# 48V_Converter.net
KiCad netlist of a schematic drawn in Altium Designer
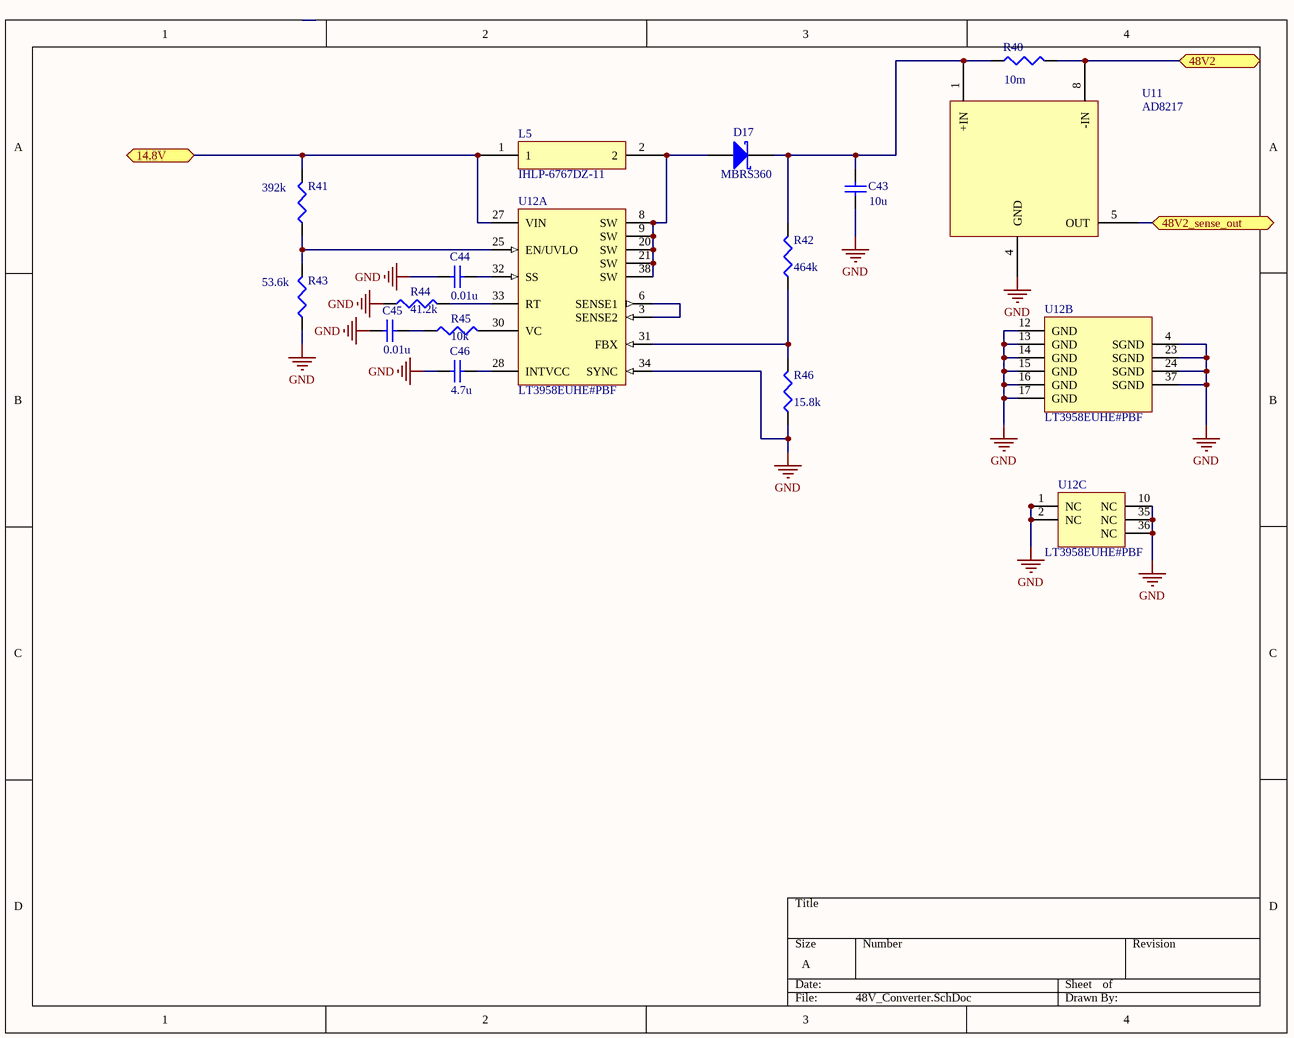
[diagram p0: 48V_Converter.SchDoc]

(export (version "E")
  (design (tool "Eeschema 10.0.6"))
  (components
    (comp (ref "C43")
      (value "10u")
      (footprint "C1206")
      (description "Capacitor (Semiconductor SIM Model)")
      (fields (field (name "Comment") "Cap Semi") (field (name "PUBLISHER") "Altium Limited"))
      (libsource (lib "Miscellaneous Devices") (part "Cap Semi"))
    )
    (comp (ref "C44")
      (value "0.01u")
      (footprint "C1206")
      (description "Capacitor (Semiconductor SIM Model)")
      (fields (field (name "Comment") "Cap Semi") (field (name "PUBLISHER") "Altium Limited"))
      (libsource (lib "Miscellaneous Devices") (part "Cap Semi"))
    )
    (comp (ref "C45")
      (value "0.01u")
      (footprint "C1206")
      (description "Capacitor (Semiconductor SIM Model)")
      (fields (field (name "Comment") "Cap Semi") (field (name "PUBLISHER") "Altium Limited"))
      (libsource (lib "Miscellaneous Devices") (part "Cap Semi"))
    )
    (comp (ref "C46")
      (value "4.7u")
      (footprint "C1206")
      (description "Capacitor (Semiconductor SIM Model)")
      (fields (field (name "Comment") "Cap Semi") (field (name "PUBLISHER") "Altium Limited"))
      (libsource (lib "Miscellaneous Devices") (part "Cap Semi"))
    )
    (comp (ref "D17")
      (value "MBRS360")
      (footprint "SMB")
      (description "Schottky Diode")
      (fields (field (name "PUBLISHER") "Altium Limited"))
      (libsource (lib "Miscellaneous Devices") (part "D Schottky"))
    )
    (comp (ref "L5")
      (value "IHLP-6767DZ-11")
      (footprint "IHLP-6767DZ-11")
      (description "Inductor")
      (libsource (lib "Integrated_Library") (part "IHLP-6767DZ-11"))
    )
    (comp (ref "R40")
      (value "10m")
      (footprint "J1-0603")
      (description "Resistor")
      (fields (field (name "Comment") "Res3") (field (name "PUBLISHER") "Altium Limited"))
      (libsource (lib "Miscellaneous Devices") (part "Res3"))
    )
    (comp (ref "R41")
      (value "392k")
      (footprint "J1-0603")
      (description "Resistor")
      (fields (field (name "Comment") "Res3") (field (name "PUBLISHER") "Altium Limited"))
      (libsource (lib "Miscellaneous Devices") (part "Res3"))
    )
    (comp (ref "R42")
      (value "464k")
      (footprint "J1-0603")
      (description "Resistor")
      (fields (field (name "Comment") "Res3") (field (name "PUBLISHER") "Altium Limited"))
      (libsource (lib "Miscellaneous Devices") (part "Res3"))
    )
    (comp (ref "R43")
      (value "53.6k")
      (footprint "J1-0603")
      (description "Resistor")
      (fields (field (name "Comment") "Res3") (field (name "PUBLISHER") "Altium Limited"))
      (libsource (lib "Miscellaneous Devices") (part "Res3"))
    )
    (comp (ref "R44")
      (value "41.2k")
      (footprint "J1-0603")
      (description "Resistor")
      (fields (field (name "Comment") "Res3") (field (name "PUBLISHER") "Altium Limited"))
      (libsource (lib "Miscellaneous Devices") (part "Res3"))
    )
    (comp (ref "R45")
      (value "10k")
      (footprint "J1-0603")
      (description "Resistor")
      (fields (field (name "Comment") "Res3") (field (name "PUBLISHER") "Altium Limited"))
      (libsource (lib "Miscellaneous Devices") (part "Res3"))
    )
    (comp (ref "R46")
      (value "15.8k")
      (footprint "J1-0603")
      (description "Resistor")
      (fields (field (name "Comment") "Res3") (field (name "PUBLISHER") "Altium Limited"))
      (libsource (lib "Miscellaneous Devices") (part "Res3"))
    )
    (comp (ref "U11")
      (value "AD8217")
      (footprint "AD8217")
      (description "Current Shunt Moniter")
      (libsource (lib "Integrated_Library") (part "AD8217"))
    )
    (comp (ref "U12")
      (value "LT3958EUHE#PBF")
      (footprint "LT3958")
      (description "LT3958")
      (fields (field (name "MANUFACTURER") "Linear Technology"))
      (libsource (lib "Integrated_Library") (part "LT3958EUHE#PBF"))
    )
  )
  (nets
    (net (code "1") (name "/14.8V") (class "Default")
      (node (ref "L5") (pin "1") (pinfunction "1_1") (pintype "passive"))
      (node (ref "R41") (pin "2") (pinfunction "2_2") (pintype "passive"))
      (node (ref "U12") (pin "27") (pinfunction "VIN_27") (pintype "power_in"))
    )
    (net (code "2") (name "/48V2") (class "Default")
      (node (ref "R40") (pin "2") (pinfunction "2_2") (pintype "passive"))
      (node (ref "U11") (pin "8") (pinfunction "-IN_8") (pintype "passive"))
    )
    (net (code "3") (name "/48V2_sense_out") (class "Default")
      (node (ref "U11") (pin "5") (pinfunction "OUT_5") (pintype "passive"))
    )
    (net (code "4") (name "GND") (class "Default")
      (node (ref "C43") (pin "1") (pinfunction "1_1") (pintype "passive"))
      (node (ref "C44") (pin "1") (pinfunction "1_1") (pintype "passive"))
      (node (ref "C45") (pin "1") (pinfunction "1_1") (pintype "passive"))
      (node (ref "C46") (pin "1") (pinfunction "1_1") (pintype "passive"))
      (node (ref "R43") (pin "1") (pinfunction "1_1") (pintype "passive"))
      (node (ref "R44") (pin "1") (pinfunction "1_1") (pintype "passive"))
      (node (ref "R46") (pin "1") (pinfunction "1_1") (pintype "passive"))
      (node (ref "U11") (pin "4") (pinfunction "GND_4") (pintype "passive"))
      (node (ref "U12") (pin "1") (pinfunction "NC_1") (pintype "passive"))
      (node (ref "U12") (pin "10") (pinfunction "NC_10") (pintype "passive"))
      (node (ref "U12") (pin "12") (pinfunction "GND_12") (pintype "power_in"))
      (node (ref "U12") (pin "13") (pinfunction "GND_13") (pintype "power_in"))
      (node (ref "U12") (pin "14") (pinfunction "GND_14") (pintype "power_in"))
      (node (ref "U12") (pin "15") (pinfunction "GND_15") (pintype "power_in"))
      (node (ref "U12") (pin "16") (pinfunction "GND_16") (pintype "power_in"))
      (node (ref "U12") (pin "17") (pinfunction "GND_17") (pintype "power_in"))
      (node (ref "U12") (pin "2") (pinfunction "NC_2") (pintype "passive"))
      (node (ref "U12") (pin "23") (pinfunction "SGND_23") (pintype "power_in"))
      (node (ref "U12") (pin "24") (pinfunction "SGND_24") (pintype "power_in"))
      (node (ref "U12") (pin "34") (pinfunction "SYNC_34") (pintype "input"))
      (node (ref "U12") (pin "35") (pinfunction "NC_35") (pintype "passive"))
      (node (ref "U12") (pin "36") (pinfunction "NC_36") (pintype "passive"))
      (node (ref "U12") (pin "37") (pinfunction "SGND_37") (pintype "power_in"))
      (node (ref "U12") (pin "4") (pinfunction "SGND_4") (pintype "power_in"))
    )
    (net (code "5") (name "Net-(C45-Pad2)") (class "Default")
      (node (ref "C45") (pin "2") (pinfunction "2_2") (pintype "passive"))
      (node (ref "R45") (pin "1") (pinfunction "1_1") (pintype "passive"))
    )
    (net (code "6") (name "Net-(D17-A)") (class "Default")
      (node (ref "D17") (pin "1") (pinfunction "A_1") (pintype "passive"))
      (node (ref "L5") (pin "2") (pinfunction "2_2") (pintype "passive"))
      (node (ref "U12") (pin "20") (pinfunction "SW_20") (pintype "power_in"))
      (node (ref "U12") (pin "21") (pinfunction "SW_21") (pintype "power_in"))
      (node (ref "U12") (pin "38") (pinfunction "SW_38") (pintype "power_in"))
      (node (ref "U12") (pin "8") (pinfunction "SW_8") (pintype "power_in"))
      (node (ref "U12") (pin "9") (pinfunction "SW_9") (pintype "power_in"))
    )
    (net (code "7") (name "Net-(D17-K)") (class "Default")
      (node (ref "C43") (pin "2") (pinfunction "2_2") (pintype "passive"))
      (node (ref "D17") (pin "2") (pinfunction "K_2") (pintype "passive"))
      (node (ref "R40") (pin "1") (pinfunction "1_1") (pintype "passive"))
      (node (ref "R42") (pin "2") (pinfunction "2_2") (pintype "passive"))
      (node (ref "U11") (pin "1") (pinfunction "+IN_1") (pintype "passive"))
    )
    (net (code "8") (name "Net-(U12A-EN{slash}UVLO)") (class "Default")
      (node (ref "R41") (pin "1") (pinfunction "1_1") (pintype "passive"))
      (node (ref "R43") (pin "2") (pinfunction "2_2") (pintype "passive"))
      (node (ref "U12") (pin "25") (pinfunction "EN/UVLO_25") (pintype "input"))
    )
    (net (code "9") (name "Net-(U12A-FBX)") (class "Default")
      (node (ref "R42") (pin "1") (pinfunction "1_1") (pintype "passive"))
      (node (ref "R46") (pin "2") (pinfunction "2_2") (pintype "passive"))
      (node (ref "U12") (pin "31") (pinfunction "FBX_31") (pintype "input"))
    )
    (net (code "10") (name "Net-(U12A-INTVCC)") (class "Default")
      (node (ref "C46") (pin "2") (pinfunction "2_2") (pintype "passive"))
      (node (ref "U12") (pin "28") (pinfunction "INTVCC_28") (pintype "power_in"))
    )
    (net (code "11") (name "Net-(U12A-RT)") (class "Default")
      (node (ref "R44") (pin "2") (pinfunction "2_2") (pintype "passive"))
      (node (ref "U12") (pin "33") (pinfunction "RT_33") (pintype "passive"))
    )
    (net (code "12") (name "Net-(U12A-SENSE1)") (class "Default")
      (node (ref "U12") (pin "3") (pinfunction "SENSE2_3") (pintype "input"))
      (node (ref "U12") (pin "6") (pinfunction "SENSE1_6") (pintype "output"))
    )
    (net (code "13") (name "Net-(U12A-SS)") (class "Default")
      (node (ref "C44") (pin "2") (pinfunction "2_2") (pintype "passive"))
      (node (ref "U12") (pin "32") (pinfunction "SS_32") (pintype "input"))
    )
    (net (code "14") (name "Net-(U12A-VC)") (class "Default")
      (node (ref "R45") (pin "2") (pinfunction "2_2") (pintype "passive"))
      (node (ref "U12") (pin "30") (pinfunction "VC_30") (pintype "passive"))
    )
  )
)
